# M165D.net
KiCad netlist of a schematic drawn in EAGLE
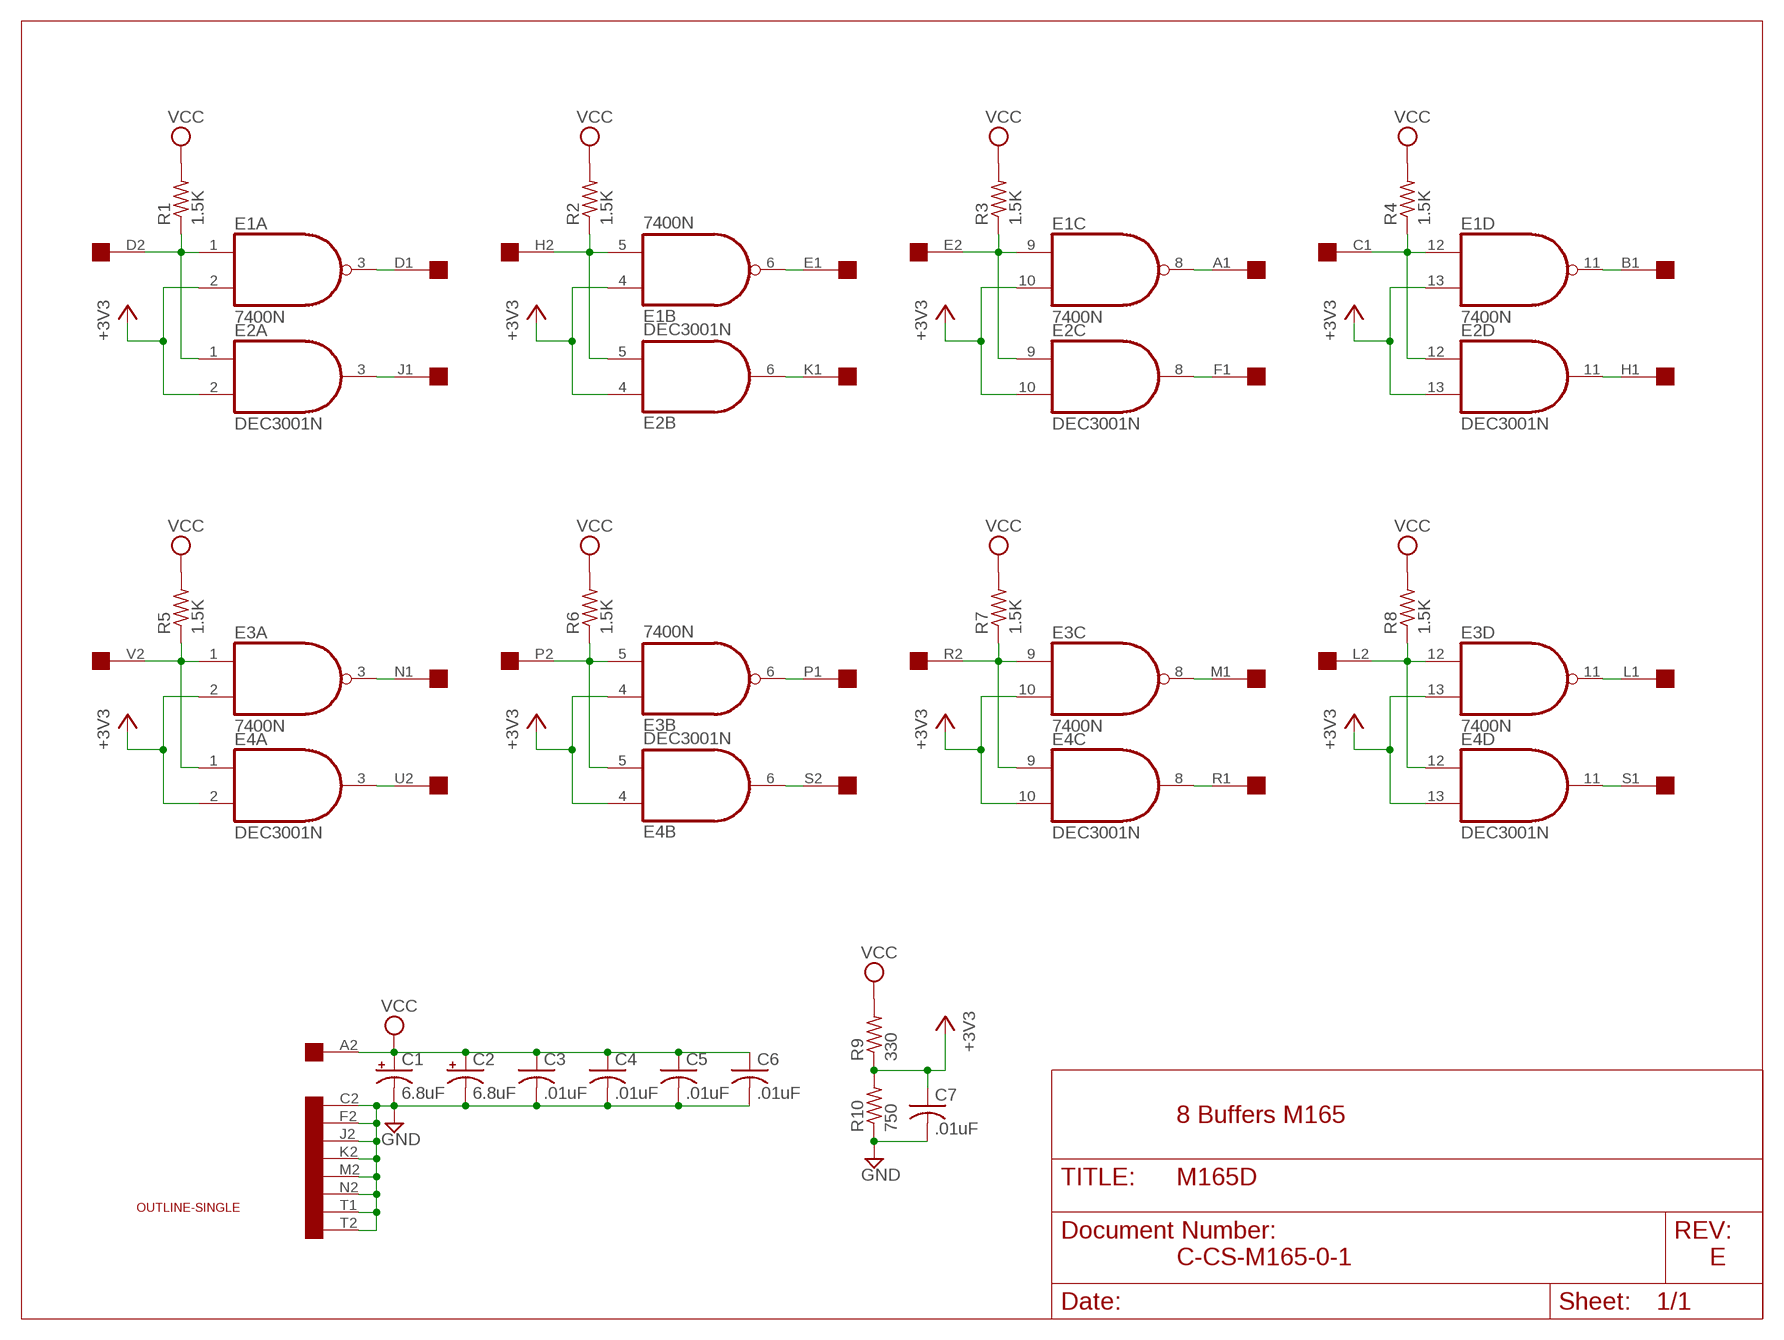
[diagram p0: schematic, sheet 1]

(export (version "E")
  (design (tool "Eeschema 10.0.6"))
  (components
    (comp (ref "C1")
      (value "6.8uF")
      (footprint "eagle-import:E25-9")
      (libsource (lib "eagle-import") (part "CPOL-USE25-9AXIAL"))
    )
    (comp (ref "C2")
      (value "6.8uF")
      (footprint "eagle-import:E25-9")
      (libsource (lib "eagle-import") (part "CPOL-USE25-9AXIAL"))
    )
    (comp (ref "C3")
      (value ".01uF")
      (footprint "eagle-import:C050-025X075")
      (libsource (lib "eagle-import") (part "C-US050-025X075"))
    )
    (comp (ref "C4")
      (value ".01uF")
      (footprint "eagle-import:C050-025X075")
      (libsource (lib "eagle-import") (part "C-US050-025X075"))
    )
    (comp (ref "C5")
      (value ".01uF")
      (footprint "eagle-import:C050-025X075")
      (libsource (lib "eagle-import") (part "C-US050-025X075"))
    )
    (comp (ref "C6")
      (value ".01uF")
      (footprint "eagle-import:C050-025X075")
      (libsource (lib "eagle-import") (part "C-US050-025X075"))
    )
    (comp (ref "C7")
      (value ".01uF")
      (footprint "eagle-import:C050-025X075")
      (libsource (lib "eagle-import") (part "C-US050-025X075"))
    )
    (comp (ref "E1")
      (value "7400N")
      (footprint "eagle-import:DIL14")
      (libsource (lib "eagle-import") (part "7400N"))
    )
    (comp (ref "E2")
      (value "DEC3001N")
      (footprint "eagle-import:DIL14")
      (libsource (lib "eagle-import") (part "7408NS"))
    )
    (comp (ref "E3")
      (value "7400N")
      (footprint "eagle-import:DIL14")
      (libsource (lib "eagle-import") (part "7400N"))
    )
    (comp (ref "E4")
      (value "DEC3001N")
      (footprint "eagle-import:DIL14")
      (libsource (lib "eagle-import") (part "7408NS"))
    )
    (comp (ref "R1")
      (value "1.5K")
      (footprint "eagle-import:0207_10")
      (libsource (lib "eagle-import") (part "R-US_0207/10"))
    )
    (comp (ref "R2")
      (value "1.5K")
      (footprint "eagle-import:0207_10")
      (libsource (lib "eagle-import") (part "R-US_0207/10"))
    )
    (comp (ref "R3")
      (value "1.5K")
      (footprint "eagle-import:0207_10")
      (libsource (lib "eagle-import") (part "R-US_0207/10"))
    )
    (comp (ref "R4")
      (value "1.5K")
      (footprint "eagle-import:0207_10")
      (libsource (lib "eagle-import") (part "R-US_0207/10"))
    )
    (comp (ref "R5")
      (value "1.5K")
      (footprint "eagle-import:0207_10")
      (libsource (lib "eagle-import") (part "R-US_0207/10"))
    )
    (comp (ref "R6")
      (value "1.5K")
      (footprint "eagle-import:0207_10")
      (libsource (lib "eagle-import") (part "R-US_0207/10"))
    )
    (comp (ref "R7")
      (value "1.5K")
      (footprint "eagle-import:0207_10")
      (libsource (lib "eagle-import") (part "R-US_0207/10"))
    )
    (comp (ref "R8")
      (value "1.5K")
      (footprint "eagle-import:0207_10")
      (libsource (lib "eagle-import") (part "R-US_0207/10"))
    )
    (comp (ref "R9")
      (value "330")
      (footprint "eagle-import:0207_10")
      (libsource (lib "eagle-import") (part "R-US_0207/10"))
    )
    (comp (ref "R10")
      (value "750")
      (footprint "eagle-import:0207_10")
      (libsource (lib "eagle-import") (part "R-US_0207/10"))
    )
    (comp (ref "U$1")
      (value "SINGLE")
      (footprint "eagle-import:EDGE-CON2")
      (libsource (lib "eagle-import") (part "SINGLE"))
    )
    (comp (ref "U$2")
      (value "OUTLINE-SINGLE")
      (footprint "eagle-import:SINGLE")
      (libsource (lib "eagle-import") (part "OUTLINE-SINGLE"))
    )
  )
  (nets
    (net (code "1") (name "+3V3") (class "Default")
      (node (ref "C7") (pin "1") (pinfunction "1_1") (pintype "passive"))
      (node (ref "E1") (pin "10") (pinfunction "I1_10") (pintype "input"))
      (node (ref "E1") (pin "13") (pinfunction "I1_13") (pintype "input"))
      (node (ref "E1") (pin "2") (pinfunction "I1_2") (pintype "input"))
      (node (ref "E1") (pin "4") (pinfunction "I0_4") (pintype "input"))
      (node (ref "E2") (pin "10") (pinfunction "I1_10") (pintype "input"))
      (node (ref "E2") (pin "13") (pinfunction "I1_13") (pintype "input"))
      (node (ref "E2") (pin "2") (pinfunction "I1_2") (pintype "input"))
      (node (ref "E2") (pin "4") (pinfunction "I0_4") (pintype "input"))
      (node (ref "E3") (pin "10") (pinfunction "I1_10") (pintype "input"))
      (node (ref "E3") (pin "13") (pinfunction "I1_13") (pintype "input"))
      (node (ref "E3") (pin "2") (pinfunction "I1_2") (pintype "input"))
      (node (ref "E3") (pin "4") (pinfunction "I0_4") (pintype "input"))
      (node (ref "E4") (pin "10") (pinfunction "I1_10") (pintype "input"))
      (node (ref "E4") (pin "13") (pinfunction "I1_13") (pintype "input"))
      (node (ref "E4") (pin "2") (pinfunction "I1_2") (pintype "input"))
      (node (ref "E4") (pin "4") (pinfunction "I0_4") (pintype "input"))
      (node (ref "R10") (pin "2") (pinfunction "2_2") (pintype "passive"))
      (node (ref "R9") (pin "1") (pinfunction "1_1") (pintype "passive"))
    )
    (net (code "2") (name "GND") (class "Default")
      (node (ref "C1") (pin "-") (pinfunction "-_-") (pintype "passive"))
      (node (ref "C2") (pin "-") (pinfunction "-_-") (pintype "passive"))
      (node (ref "C3") (pin "2") (pinfunction "2_2") (pintype "passive"))
      (node (ref "C4") (pin "2") (pinfunction "2_2") (pintype "passive"))
      (node (ref "C5") (pin "2") (pinfunction "2_2") (pintype "passive"))
      (node (ref "C6") (pin "2") (pinfunction "2_2") (pintype "passive"))
      (node (ref "C7") (pin "2") (pinfunction "2_2") (pintype "passive"))
      (node (ref "R10") (pin "1") (pinfunction "1_1") (pintype "passive"))
      (node (ref "U$1") (pin "C2") (pinfunction "1_C2") (pintype "bidirectional"))
      (node (ref "U$1") (pin "F2") (pinfunction "1_F2") (pintype "bidirectional"))
      (node (ref "U$1") (pin "J2") (pinfunction "1_J2") (pintype "bidirectional"))
      (node (ref "U$1") (pin "K2") (pinfunction "1_K2") (pintype "bidirectional"))
      (node (ref "U$1") (pin "M2") (pinfunction "1_M2") (pintype "bidirectional"))
      (node (ref "U$1") (pin "N2") (pinfunction "1_N2") (pintype "bidirectional"))
      (node (ref "U$1") (pin "T1") (pinfunction "1_T1") (pintype "bidirectional"))
      (node (ref "U$1") (pin "T2") (pinfunction "1_T2") (pintype "bidirectional"))
    )
    (net (code "3") (name "Net-(E1A-I0)") (class "Default")
      (node (ref "E1") (pin "1") (pinfunction "I0_1") (pintype "input"))
      (node (ref "E2") (pin "1") (pinfunction "I0_1") (pintype "input"))
      (node (ref "R1") (pin "1") (pinfunction "1_1") (pintype "passive"))
      (node (ref "U$1") (pin "D2") (pinfunction "1_D2") (pintype "bidirectional"))
    )
    (net (code "4") (name "Net-(E1A-O)") (class "Default")
      (node (ref "E1") (pin "3") (pinfunction "O_3") (pintype "output"))
      (node (ref "U$1") (pin "D1") (pinfunction "1_D1") (pintype "bidirectional"))
    )
    (net (code "5") (name "Net-(E1B-I1)") (class "Default")
      (node (ref "E1") (pin "5") (pinfunction "I1_5") (pintype "input"))
      (node (ref "E2") (pin "5") (pinfunction "I1_5") (pintype "input"))
      (node (ref "R2") (pin "1") (pinfunction "1_1") (pintype "passive"))
      (node (ref "U$1") (pin "H2") (pinfunction "1_H2") (pintype "bidirectional"))
    )
    (net (code "6") (name "Net-(E1B-O)") (class "Default")
      (node (ref "E1") (pin "6") (pinfunction "O_6") (pintype "output"))
      (node (ref "U$1") (pin "E1") (pinfunction "1_E1") (pintype "bidirectional"))
    )
    (net (code "7") (name "Net-(E1C-I0)") (class "Default")
      (node (ref "E1") (pin "9") (pinfunction "I0_9") (pintype "input"))
      (node (ref "E2") (pin "9") (pinfunction "I0_9") (pintype "input"))
      (node (ref "R3") (pin "1") (pinfunction "1_1") (pintype "passive"))
      (node (ref "U$1") (pin "E2") (pinfunction "1_E2") (pintype "bidirectional"))
    )
    (net (code "8") (name "Net-(E1C-O)") (class "Default")
      (node (ref "E1") (pin "8") (pinfunction "O_8") (pintype "output"))
      (node (ref "U$1") (pin "A1") (pinfunction "1_A1") (pintype "bidirectional"))
    )
    (net (code "9") (name "Net-(E1D-I0)") (class "Default")
      (node (ref "E1") (pin "12") (pinfunction "I0_12") (pintype "input"))
      (node (ref "E2") (pin "12") (pinfunction "I0_12") (pintype "input"))
      (node (ref "R4") (pin "1") (pinfunction "1_1") (pintype "passive"))
      (node (ref "U$1") (pin "C1") (pinfunction "1_C1") (pintype "bidirectional"))
    )
    (net (code "10") (name "Net-(E1D-O)") (class "Default")
      (node (ref "E1") (pin "11") (pinfunction "O_11") (pintype "output"))
      (node (ref "U$1") (pin "B1") (pinfunction "1_B1") (pintype "bidirectional"))
    )
    (net (code "11") (name "Net-(E2A-O)") (class "Default")
      (node (ref "E2") (pin "3") (pinfunction "O_3") (pintype "output"))
      (node (ref "U$1") (pin "J1") (pinfunction "1_J1") (pintype "bidirectional"))
    )
    (net (code "12") (name "Net-(E2B-O)") (class "Default")
      (node (ref "E2") (pin "6") (pinfunction "O_6") (pintype "output"))
      (node (ref "U$1") (pin "K1") (pinfunction "1_K1") (pintype "bidirectional"))
    )
    (net (code "13") (name "Net-(E2C-O)") (class "Default")
      (node (ref "E2") (pin "8") (pinfunction "O_8") (pintype "output"))
      (node (ref "U$1") (pin "F1") (pinfunction "1_F1") (pintype "bidirectional"))
    )
    (net (code "14") (name "Net-(E2D-O)") (class "Default")
      (node (ref "E2") (pin "11") (pinfunction "O_11") (pintype "output"))
      (node (ref "U$1") (pin "H1") (pinfunction "1_H1") (pintype "bidirectional"))
    )
    (net (code "15") (name "Net-(E3A-I0)") (class "Default")
      (node (ref "E3") (pin "1") (pinfunction "I0_1") (pintype "input"))
      (node (ref "E4") (pin "1") (pinfunction "I0_1") (pintype "input"))
      (node (ref "R5") (pin "1") (pinfunction "1_1") (pintype "passive"))
      (node (ref "U$1") (pin "V2") (pinfunction "1_V2") (pintype "bidirectional"))
    )
    (net (code "16") (name "Net-(E3A-O)") (class "Default")
      (node (ref "E3") (pin "3") (pinfunction "O_3") (pintype "output"))
      (node (ref "U$1") (pin "N1") (pinfunction "1_N1") (pintype "bidirectional"))
    )
    (net (code "17") (name "Net-(E3B-I1)") (class "Default")
      (node (ref "E3") (pin "5") (pinfunction "I1_5") (pintype "input"))
      (node (ref "E4") (pin "5") (pinfunction "I1_5") (pintype "input"))
      (node (ref "R6") (pin "1") (pinfunction "1_1") (pintype "passive"))
      (node (ref "U$1") (pin "P2") (pinfunction "1_P2") (pintype "bidirectional"))
    )
    (net (code "18") (name "Net-(E3B-O)") (class "Default")
      (node (ref "E3") (pin "6") (pinfunction "O_6") (pintype "output"))
      (node (ref "U$1") (pin "P1") (pinfunction "1_P1") (pintype "bidirectional"))
    )
    (net (code "19") (name "Net-(E3C-I0)") (class "Default")
      (node (ref "E3") (pin "9") (pinfunction "I0_9") (pintype "input"))
      (node (ref "E4") (pin "9") (pinfunction "I0_9") (pintype "input"))
      (node (ref "R7") (pin "1") (pinfunction "1_1") (pintype "passive"))
      (node (ref "U$1") (pin "R2") (pinfunction "1_R2") (pintype "bidirectional"))
    )
    (net (code "20") (name "Net-(E3C-O)") (class "Default")
      (node (ref "E3") (pin "8") (pinfunction "O_8") (pintype "output"))
      (node (ref "U$1") (pin "M1") (pinfunction "1_M1") (pintype "bidirectional"))
    )
    (net (code "21") (name "Net-(E3D-I0)") (class "Default")
      (node (ref "E3") (pin "12") (pinfunction "I0_12") (pintype "input"))
      (node (ref "E4") (pin "12") (pinfunction "I0_12") (pintype "input"))
      (node (ref "R8") (pin "1") (pinfunction "1_1") (pintype "passive"))
      (node (ref "U$1") (pin "L2") (pinfunction "1_L2") (pintype "bidirectional"))
    )
    (net (code "22") (name "Net-(E3D-O)") (class "Default")
      (node (ref "E3") (pin "11") (pinfunction "O_11") (pintype "output"))
      (node (ref "U$1") (pin "L1") (pinfunction "1_L1") (pintype "bidirectional"))
    )
    (net (code "23") (name "Net-(E4A-O)") (class "Default")
      (node (ref "E4") (pin "3") (pinfunction "O_3") (pintype "output"))
      (node (ref "U$1") (pin "U2") (pinfunction "1_U2") (pintype "bidirectional"))
    )
    (net (code "24") (name "Net-(E4B-O)") (class "Default")
      (node (ref "E4") (pin "6") (pinfunction "O_6") (pintype "output"))
      (node (ref "U$1") (pin "S2") (pinfunction "1_S2") (pintype "bidirectional"))
    )
    (net (code "25") (name "Net-(E4C-O)") (class "Default")
      (node (ref "E4") (pin "8") (pinfunction "O_8") (pintype "output"))
      (node (ref "U$1") (pin "R1") (pinfunction "1_R1") (pintype "bidirectional"))
    )
    (net (code "26") (name "Net-(E4D-O)") (class "Default")
      (node (ref "E4") (pin "11") (pinfunction "O_11") (pintype "output"))
      (node (ref "U$1") (pin "S1") (pinfunction "1_S1") (pintype "bidirectional"))
    )
    (net (code "27") (name "VCC") (class "Default")
      (node (ref "C1") (pin "+") (pinfunction "+_+") (pintype "passive"))
      (node (ref "C2") (pin "+") (pinfunction "+_+") (pintype "passive"))
      (node (ref "C3") (pin "1") (pinfunction "1_1") (pintype "passive"))
      (node (ref "C4") (pin "1") (pinfunction "1_1") (pintype "passive"))
      (node (ref "C5") (pin "1") (pinfunction "1_1") (pintype "passive"))
      (node (ref "C6") (pin "1") (pinfunction "1_1") (pintype "passive"))
      (node (ref "R1") (pin "2") (pinfunction "2_2") (pintype "passive"))
      (node (ref "R2") (pin "2") (pinfunction "2_2") (pintype "passive"))
      (node (ref "R3") (pin "2") (pinfunction "2_2") (pintype "passive"))
      (node (ref "R4") (pin "2") (pinfunction "2_2") (pintype "passive"))
      (node (ref "R5") (pin "2") (pinfunction "2_2") (pintype "passive"))
      (node (ref "R6") (pin "2") (pinfunction "2_2") (pintype "passive"))
      (node (ref "R7") (pin "2") (pinfunction "2_2") (pintype "passive"))
      (node (ref "R8") (pin "2") (pinfunction "2_2") (pintype "passive"))
      (node (ref "R9") (pin "2") (pinfunction "2_2") (pintype "passive"))
      (node (ref "U$1") (pin "A2") (pinfunction "1_A2") (pintype "bidirectional"))
    )
  )
)
